# card.net
KiCad netlist of a schematic drawn in Altium Designer
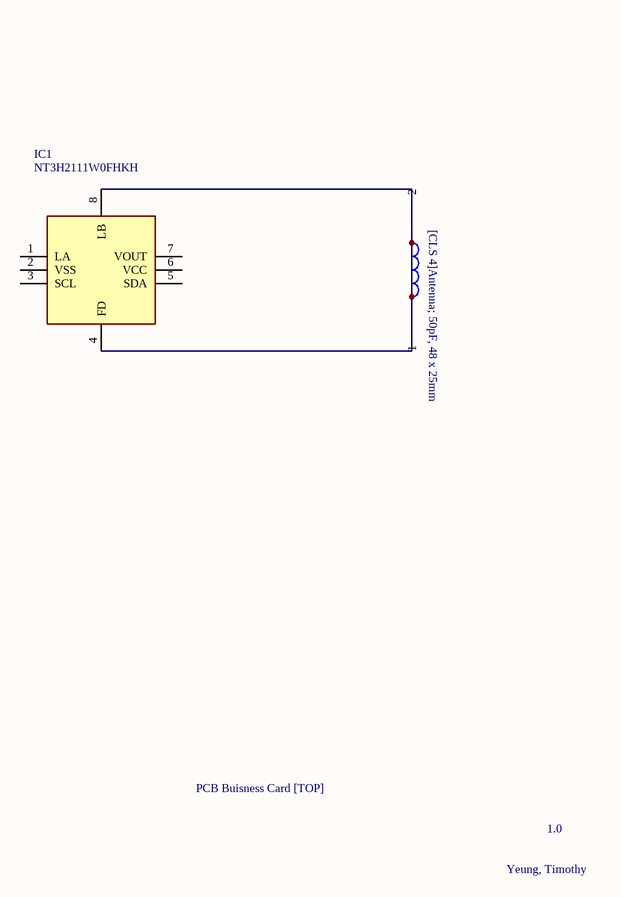
[diagram p0: card.SchDoc]

(export (version "E")
  (design (tool "Eeschema 10.0.6"))
  (components
    (comp (ref "*")
      (value "Antenna_Class4")
      (footprint "Class4_Antenna")
      (libsource (lib "card-general") (part "Antenna_Class4"))
    )
    (comp (ref "IC1")
      (value "NT3H2111W0FHKH")
      (footprint "NT3H2211W0FHK:QFN50P160X160X50-8N")
      (description "Integrated Circuit")
      (fields (field (name "MOUSER PART NUMBER") "771-NT3H2111W0FHKH"))
      (libsource (lib "*") (part "NT3H2111W0FHKH"))
    )
  )
  (nets
    (net (code "1") (name "Net-(IC1-FD)") (class "Default")
      (node (ref "*") (pin "1") (pinfunction "1_1") (pintype "passive"))
      (node (ref "*") (pin "2") (pinfunction "2_2") (pintype "passive"))
      (node (ref "IC1") (pin "4") (pinfunction "FD_4") (pintype "passive"))
      (node (ref "IC1") (pin "8") (pinfunction "LB_8") (pintype "passive"))
    )
    (net (code "2") (name "unconnected-(IC1-LA-Pad1)") (class "Default")
      (node (ref "IC1") (pin "1") (pinfunction "LA_1") (pintype "passive"))
    )
    (net (code "3") (name "unconnected-(IC1-SCL-Pad3)") (class "Default")
      (node (ref "IC1") (pin "3") (pinfunction "SCL_3") (pintype "passive"))
    )
    (net (code "4") (name "unconnected-(IC1-SDA-Pad5)") (class "Default")
      (node (ref "IC1") (pin "5") (pinfunction "SDA_5") (pintype "passive"))
    )
    (net (code "5") (name "unconnected-(IC1-VCC-Pad6)") (class "Default")
      (node (ref "IC1") (pin "6") (pinfunction "VCC_6") (pintype "passive"))
    )
    (net (code "6") (name "unconnected-(IC1-VOUT-Pad7)") (class "Default")
      (node (ref "IC1") (pin "7") (pinfunction "VOUT_7") (pintype "passive"))
    )
    (net (code "7") (name "unconnected-(IC1-VSS-Pad2)") (class "Default")
      (node (ref "IC1") (pin "2") (pinfunction "VSS_2") (pintype "passive"))
    )
  )
)
